# SCH_micro65_2023-10-09.net
KiCad netlist of a schematic drawn in EasyEDA
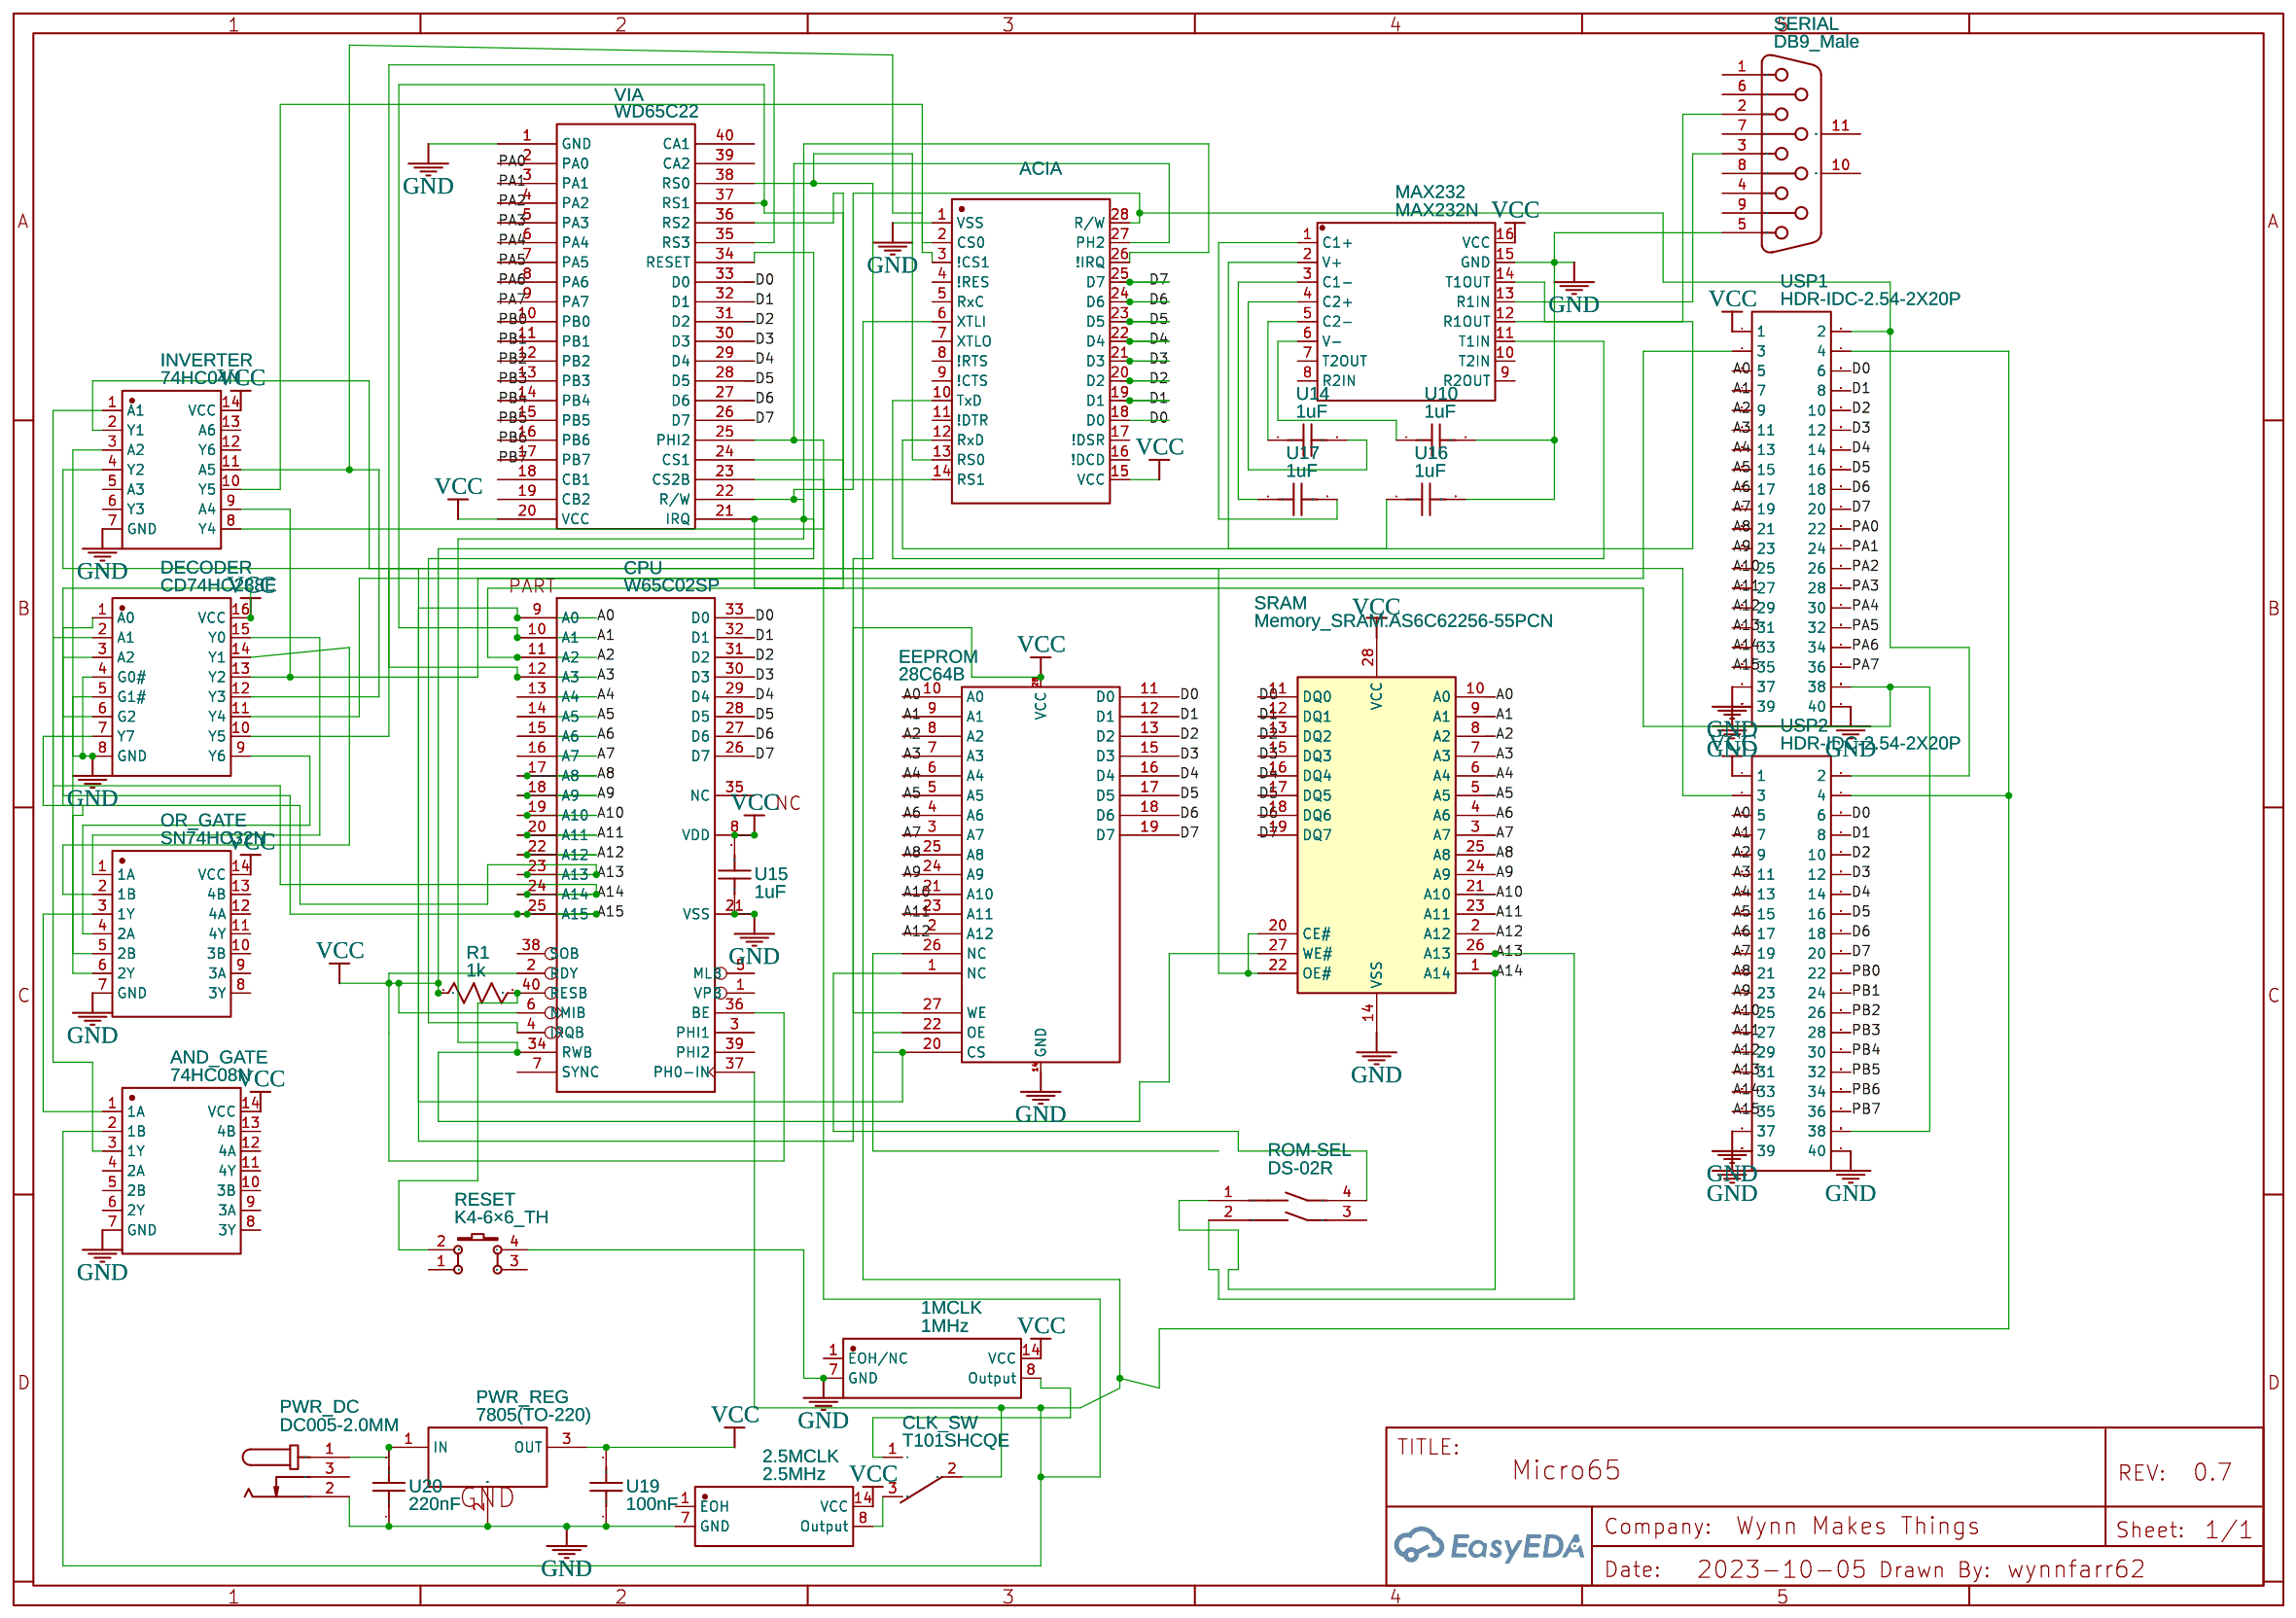
[diagram p0: schematic sheet]

(export (version "E")
  (design (tool "Eeschema 10.0.6"))
  (components
    (comp (ref "1MCLK")
      (value "1MHz")
      (fields
        (field (name "Manufacturer Part") "MXO45T-2C-1M000000")
        (field (name "Manufacturer") "CTS(西迪斯)")
      )
      (libsource (lib "") (part "MXO45T-2C-1M000000"))
    )
    (comp (ref "2.5MCLK")
      (value "2.5MHz")
      (fields
        (field (name "Manufacturer Part") "MXO45HST-2I-2M500000")
        (field (name "Manufacturer") "CTS(西迪斯)")
      )
      (libsource (lib "") (part "MXO45HST-2I-2M500000"))
    )
    (comp (ref "ACIA") (value "NO") (libsource (lib "") (part "R6551")))
    (comp (ref "AND_GATE")
      (value "74HC08N")
      (fields (field (name "Manufacturer") "HGSEMI(华冠)"))
      (libsource (lib "") (part "74HC08N"))
    )
    (comp (ref "CLK_SW")
      (value "T101SHCQE")
      (fields (field (name "Manufacturer") "C&K"))
      (libsource (lib "") (part "T101SHCQE"))
    )
    (comp (ref "CPU") (value "W65C02SP") (libsource (lib "") (part "Unknown_325_-395")))
    (comp (ref "DECODER")
      (value "CD74HC238E")
      (fields (field (name "Manufacturer") "TI(德州仪器)"))
      (libsource (lib "") (part "CD74HC238E"))
    )
    (comp (ref "EEPROM") (value "28C64B") (libsource (lib "") (part "Unknown_520_-370")))
    (comp (ref "INVERTER")
      (value "74HC04N")
      (fields (field (name "Manufacturer") "HGSEMI(华冠)"))
      (libsource (lib "") (part "74HC04N"))
    )
    (comp (ref "MAX232")
      (value "MAX232N")
      (fields (field (name "Manufacturer") "Texas Instruments"))
      (libsource (lib "") (part "MAX232N"))
    )
    (comp (ref "OR_GATE")
      (value "SN74HC32N")
      (fields (field (name "Manufacturer") "TI(德州仪器)"))
      (libsource (lib "") (part "SN74HC32N"))
    )
    (comp (ref "PWR_DC")
      (value "DC005-2.0MM")
      (fields (field (name "Manufacturer") "SOFNG"))
      (libsource (lib "") (part "DC005-2.0MM"))
    )
    (comp (ref "PWR_REG")
      (value "7805(TO-220)")
      (fields
        (field (name "Manufacturer Part") "L7805CV-DG")
        (field (name "Manufacturer") "STMicroelectronics")
      )
      (libsource (lib "") (part "7805(TO-220)"))
    )
    (comp (ref "R1") (value "1k") (libsource (lib "") (part "R_AXIAL-0.3_US")))
    (comp (ref "RESET")
      (value "K4-6×6_TH")
      (fields (field (name "Manufacturer Part") "K2-1102DP-E4SW-04") (field (name "Manufacturer") "韩国韩荣"))
      (libsource (lib "") (part "K4-6×6_TH"))
    )
    (comp (ref "ROM-SEL")
      (value "DS-02R")
      (fields (field (name "Manufacturer") "SM Switch"))
      (libsource (lib "") (part "DS-02R"))
    )
    (comp (ref "SERIAL")
      (value "DB9_Male")
      (fields (field (name "Manufacturer") "Amphenol"))
      (libsource (lib "") (part "DB9_Male"))
    )
    (comp (ref "SRAM") (value "Memory_SRAM:AS6C62256-55PCN") (libsource (lib "") (part "Unknown_690_-390")))
    (comp (ref "U10")
      (value "1uF")
      (fields (field (name "Manufacturer Part") "FK28X5R1E105KR000") (field (name "Manufacturer") "TDK"))
      (libsource (lib "") (part "FK28X5R1E105KR000_1"))
    )
    (comp (ref "U14")
      (value "1uF")
      (fields (field (name "Manufacturer Part") "FK28X5R1E105KR000") (field (name "Manufacturer") "TDK"))
      (libsource (lib "") (part "FK28X5R1E105KR000_1"))
    )
    (comp (ref "U15")
      (value "1uF")
      (fields (field (name "Manufacturer Part") "FK28X5R1E105KR000") (field (name "Manufacturer") "TDK"))
      (libsource (lib "") (part "FK28X5R1E105KR000"))
    )
    (comp (ref "U16")
      (value "1uF")
      (fields (field (name "Manufacturer Part") "FK28X5R1E105KR000") (field (name "Manufacturer") "TDK"))
      (libsource (lib "") (part "FK28X5R1E105KR000_1"))
    )
    (comp (ref "U17")
      (value "1uF")
      (fields (field (name "Manufacturer Part") "FK28X5R1E105KR000") (field (name "Manufacturer") "TDK"))
      (libsource (lib "") (part "FK28X5R1E105KR000_1"))
    )
    (comp (ref "U19")
      (value "100nF")
      (fields
        (field (name "Manufacturer Part") "MEB104J63V82CB0236")
        (field (name "Manufacturer") "KNSCHA(科尼盛)")
      )
      (libsource (lib "") (part "MEB104J63V82CB0236"))
    )
    (comp (ref "U20")
      (value "220nF")
      (fields
        (field (name "Manufacturer Part") "C242A224J20C000")
        (field (name "Manufacturer") "faratronic(厦门法拉)")
      )
      (libsource (lib "") (part "C242A224J20C000"))
    )
    (comp (ref "USP1")
      (value "HDR-IDC-2.54-2X20P")
      (fields
        (field (name "Manufacturer Part") "IDC Box 2X20 2.54MM")
        (field (name "Manufacturer") "BOOMELE")
      )
      (libsource (lib "") (part "HDR-IDC-2.54-2X20P"))
    )
    (comp (ref "USP2")
      (value "HDR-IDC-2.54-2X20P")
      (fields
        (field (name "Manufacturer Part") "IDC Box 2X20 2.54MM")
        (field (name "Manufacturer") "BOOMELE")
      )
      (libsource (lib "") (part "HDR-IDC-2.54-2X20P"))
    )
    (comp (ref "VIA") (value "WD65C22") (libsource (lib "") (part "Unknown_310_-650")))
  )
  (nets
    (net (code "1") (name "/A0") (class "Default")
      (node (ref "ACIA") (pin "13") (pinfunction "RS0_13") (pintype "unspecified"))
      (node (ref "CPU") (pin "9") (pinfunction "A0_9") (pintype "unspecified"))
      (node (ref "EEPROM") (pin "10") (pinfunction "A0_10") (pintype "input"))
      (node (ref "SRAM") (pin "10") (pinfunction "A0_10") (pintype "input"))
      (node (ref "USP1") (pin "5") (pinfunction "5_5") (pintype "unspecified"))
      (node (ref "USP2") (pin "5") (pinfunction "5_5") (pintype "unspecified"))
      (node (ref "VIA") (pin "38") (pinfunction "RS0_38") (pintype "input"))
    )
    (net (code "2") (name "/A1") (class "Default")
      (node (ref "ACIA") (pin "14") (pinfunction "RS1_14") (pintype "unspecified"))
      (node (ref "CPU") (pin "10") (pinfunction "A1_10") (pintype "unspecified"))
      (node (ref "EEPROM") (pin "9") (pinfunction "A1_9") (pintype "input"))
      (node (ref "SRAM") (pin "9") (pinfunction "A1_9") (pintype "input"))
      (node (ref "USP1") (pin "7") (pinfunction "7_7") (pintype "unspecified"))
      (node (ref "USP2") (pin "7") (pinfunction "7_7") (pintype "unspecified"))
      (node (ref "VIA") (pin "37") (pinfunction "RS1_37") (pintype "input"))
    )
    (net (code "3") (name "/A2") (class "Default")
      (node (ref "CPU") (pin "11") (pinfunction "A2_11") (pintype "unspecified"))
      (node (ref "EEPROM") (pin "8") (pinfunction "A2_8") (pintype "input"))
      (node (ref "SRAM") (pin "8") (pinfunction "A2_8") (pintype "input"))
      (node (ref "USP1") (pin "9") (pinfunction "9_9") (pintype "unspecified"))
      (node (ref "USP2") (pin "9") (pinfunction "9_9") (pintype "unspecified"))
      (node (ref "VIA") (pin "36") (pinfunction "RS2_36") (pintype "input"))
    )
    (net (code "4") (name "/A3") (class "Default")
      (node (ref "CPU") (pin "12") (pinfunction "A3_12") (pintype "unspecified"))
      (node (ref "EEPROM") (pin "7") (pinfunction "A3_7") (pintype "input"))
      (node (ref "SRAM") (pin "7") (pinfunction "A3_7") (pintype "input"))
      (node (ref "USP1") (pin "11") (pinfunction "11_11") (pintype "unspecified"))
      (node (ref "USP2") (pin "11") (pinfunction "11_11") (pintype "unspecified"))
      (node (ref "VIA") (pin "35") (pinfunction "RS3_35") (pintype "input"))
    )
    (net (code "5") (name "/A4") (class "Default")
      (node (ref "CPU") (pin "13") (pinfunction "A4_13") (pintype "unspecified"))
      (node (ref "EEPROM") (pin "6") (pinfunction "A4_6") (pintype "input"))
      (node (ref "SRAM") (pin "6") (pinfunction "A4_6") (pintype "input"))
      (node (ref "USP1") (pin "13") (pinfunction "13_13") (pintype "unspecified"))
      (node (ref "USP2") (pin "13") (pinfunction "13_13") (pintype "unspecified"))
    )
    (net (code "6") (name "/A5") (class "Default")
      (node (ref "CPU") (pin "14") (pinfunction "A5_14") (pintype "unspecified"))
      (node (ref "EEPROM") (pin "5") (pinfunction "A5_5") (pintype "input"))
      (node (ref "SRAM") (pin "5") (pinfunction "A5_5") (pintype "input"))
      (node (ref "USP1") (pin "15") (pinfunction "15_15") (pintype "unspecified"))
      (node (ref "USP2") (pin "15") (pinfunction "15_15") (pintype "unspecified"))
    )
    (net (code "7") (name "/A6") (class "Default")
      (node (ref "CPU") (pin "15") (pinfunction "A6_15") (pintype "unspecified"))
      (node (ref "EEPROM") (pin "4") (pinfunction "A6_4") (pintype "input"))
      (node (ref "SRAM") (pin "4") (pinfunction "A6_4") (pintype "input"))
      (node (ref "USP1") (pin "17") (pinfunction "17_17") (pintype "unspecified"))
      (node (ref "USP2") (pin "17") (pinfunction "17_17") (pintype "unspecified"))
    )
    (net (code "8") (name "/A7") (class "Default")
      (node (ref "CPU") (pin "16") (pinfunction "A7_16") (pintype "unspecified"))
      (node (ref "EEPROM") (pin "3") (pinfunction "A7_3") (pintype "input"))
      (node (ref "SRAM") (pin "3") (pinfunction "A7_3") (pintype "input"))
      (node (ref "USP1") (pin "19") (pinfunction "19_19") (pintype "unspecified"))
      (node (ref "USP2") (pin "19") (pinfunction "19_19") (pintype "unspecified"))
    )
    (net (code "9") (name "/A8") (class "Default")
      (node (ref "CPU") (pin "17") (pinfunction "A8_17") (pintype "unspecified"))
      (node (ref "EEPROM") (pin "25") (pinfunction "A8_25") (pintype "input"))
      (node (ref "SRAM") (pin "25") (pinfunction "A8_25") (pintype "input"))
      (node (ref "USP1") (pin "21") (pinfunction "21_21") (pintype "unspecified"))
      (node (ref "USP2") (pin "21") (pinfunction "21_21") (pintype "unspecified"))
    )
    (net (code "10") (name "/A9") (class "Default")
      (node (ref "CPU") (pin "18") (pinfunction "A9_18") (pintype "unspecified"))
      (node (ref "EEPROM") (pin "24") (pinfunction "A9_24") (pintype "input"))
      (node (ref "SRAM") (pin "24") (pinfunction "A9_24") (pintype "input"))
      (node (ref "USP1") (pin "23") (pinfunction "23_23") (pintype "unspecified"))
      (node (ref "USP2") (pin "23") (pinfunction "23_23") (pintype "unspecified"))
    )
    (net (code "11") (name "/A10") (class "Default")
      (node (ref "CPU") (pin "19") (pinfunction "A10_19") (pintype "unspecified"))
      (node (ref "EEPROM") (pin "21") (pinfunction "A10_21") (pintype "input"))
      (node (ref "SRAM") (pin "21") (pinfunction "A10_21") (pintype "input"))
      (node (ref "USP1") (pin "25") (pinfunction "25_25") (pintype "unspecified"))
      (node (ref "USP2") (pin "25") (pinfunction "25_25") (pintype "unspecified"))
    )
    (net (code "12") (name "/A11") (class "Default")
      (node (ref "CPU") (pin "20") (pinfunction "A11_20") (pintype "unspecified"))
      (node (ref "EEPROM") (pin "23") (pinfunction "A11_23") (pintype "input"))
      (node (ref "SRAM") (pin "23") (pinfunction "A11_23") (pintype "input"))
      (node (ref "USP1") (pin "27") (pinfunction "27_27") (pintype "unspecified"))
      (node (ref "USP2") (pin "27") (pinfunction "27_27") (pintype "unspecified"))
    )
    (net (code "13") (name "/A12") (class "Default")
      (node (ref "CPU") (pin "22") (pinfunction "A12_22") (pintype "unspecified"))
      (node (ref "EEPROM") (pin "2") (pinfunction "A12_2") (pintype "input"))
      (node (ref "SRAM") (pin "2") (pinfunction "A12_2") (pintype "input"))
      (node (ref "USP1") (pin "29") (pinfunction "29_29") (pintype "unspecified"))
      (node (ref "USP2") (pin "29") (pinfunction "29_29") (pintype "unspecified"))
    )
    (net (code "14") (name "/A13") (class "Default")
      (node (ref "CPU") (pin "23") (pinfunction "A13_23") (pintype "unspecified"))
      (node (ref "DECODER") (pin "1") (pinfunction "A0_1") (pintype "unspecified"))
      (node (ref "ROM-SEL") (pin "2") (pinfunction "2_2") (pintype "unspecified"))
      (node (ref "SRAM") (pin "26") (pinfunction "A13_26") (pintype "input"))
      (node (ref "USP1") (pin "31") (pinfunction "31_31") (pintype "unspecified"))
      (node (ref "USP2") (pin "31") (pinfunction "31_31") (pintype "unspecified"))
    )
    (net (code "15") (name "/A14") (class "Default")
      (node (ref "CPU") (pin "24") (pinfunction "A14_24") (pintype "unspecified"))
      (node (ref "DECODER") (pin "2") (pinfunction "A1_2") (pintype "unspecified"))
      (node (ref "ROM-SEL") (pin "1") (pinfunction "1_1") (pintype "unspecified"))
      (node (ref "SRAM") (pin "1") (pinfunction "A14_1") (pintype "input"))
      (node (ref "USP1") (pin "33") (pinfunction "33_33") (pintype "unspecified"))
      (node (ref "USP2") (pin "33") (pinfunction "33_33") (pintype "unspecified"))
    )
    (net (code "16") (name "/A15") (class "Default")
      (node (ref "CPU") (pin "25") (pinfunction "A15_25") (pintype "unspecified"))
      (node (ref "DECODER") (pin "3") (pinfunction "A2_3") (pintype "unspecified"))
      (node (ref "USP1") (pin "35") (pinfunction "35_35") (pintype "unspecified"))
      (node (ref "USP2") (pin "35") (pinfunction "35_35") (pintype "unspecified"))
    )
    (net (code "17") (name "/D0") (class "Default")
      (node (ref "ACIA") (pin "18") (pinfunction "D0_18") (pintype "unspecified"))
      (node (ref "CPU") (pin "33") (pinfunction "D0_33") (pintype "unspecified"))
      (node (ref "EEPROM") (pin "11") (pinfunction "D0_11") (pintype "bidirectional"))
      (node (ref "SRAM") (pin "11") (pinfunction "DQ0_11") (pintype "bidirectional"))
      (node (ref "USP1") (pin "6") (pinfunction "6_6") (pintype "unspecified"))
      (node (ref "USP2") (pin "6") (pinfunction "6_6") (pintype "unspecified"))
      (node (ref "VIA") (pin "33") (pinfunction "D0_33") (pintype "bidirectional"))
    )
    (net (code "18") (name "/D1") (class "Default")
      (node (ref "ACIA") (pin "19") (pinfunction "D1_19") (pintype "unspecified"))
      (node (ref "CPU") (pin "32") (pinfunction "D1_32") (pintype "unspecified"))
      (node (ref "EEPROM") (pin "12") (pinfunction "D1_12") (pintype "bidirectional"))
      (node (ref "SRAM") (pin "12") (pinfunction "DQ1_12") (pintype "bidirectional"))
      (node (ref "USP1") (pin "8") (pinfunction "8_8") (pintype "unspecified"))
      (node (ref "USP2") (pin "8") (pinfunction "8_8") (pintype "unspecified"))
      (node (ref "VIA") (pin "32") (pinfunction "D1_32") (pintype "bidirectional"))
    )
    (net (code "19") (name "/D2") (class "Default")
      (node (ref "ACIA") (pin "20") (pinfunction "D2_20") (pintype "unspecified"))
      (node (ref "CPU") (pin "31") (pinfunction "D2_31") (pintype "unspecified"))
      (node (ref "EEPROM") (pin "13") (pinfunction "D2_13") (pintype "bidirectional"))
      (node (ref "SRAM") (pin "13") (pinfunction "DQ2_13") (pintype "bidirectional"))
      (node (ref "USP1") (pin "10") (pinfunction "10_10") (pintype "unspecified"))
      (node (ref "USP2") (pin "10") (pinfunction "10_10") (pintype "unspecified"))
      (node (ref "VIA") (pin "31") (pinfunction "D2_31") (pintype "bidirectional"))
    )
    (net (code "20") (name "/D3") (class "Default")
      (node (ref "ACIA") (pin "21") (pinfunction "D3_21") (pintype "unspecified"))
      (node (ref "CPU") (pin "30") (pinfunction "D3_30") (pintype "unspecified"))
      (node (ref "EEPROM") (pin "15") (pinfunction "D3_15") (pintype "bidirectional"))
      (node (ref "SRAM") (pin "15") (pinfunction "DQ3_15") (pintype "bidirectional"))
      (node (ref "USP1") (pin "12") (pinfunction "12_12") (pintype "unspecified"))
      (node (ref "USP2") (pin "12") (pinfunction "12_12") (pintype "unspecified"))
      (node (ref "VIA") (pin "30") (pinfunction "D3_30") (pintype "bidirectional"))
    )
    (net (code "21") (name "/D4") (class "Default")
      (node (ref "ACIA") (pin "22") (pinfunction "D4_22") (pintype "unspecified"))
      (node (ref "CPU") (pin "29") (pinfunction "D4_29") (pintype "unspecified"))
      (node (ref "EEPROM") (pin "16") (pinfunction "D4_16") (pintype "bidirectional"))
      (node (ref "SRAM") (pin "16") (pinfunction "DQ4_16") (pintype "bidirectional"))
      (node (ref "USP1") (pin "14") (pinfunction "14_14") (pintype "unspecified"))
      (node (ref "USP2") (pin "14") (pinfunction "14_14") (pintype "unspecified"))
      (node (ref "VIA") (pin "29") (pinfunction "D4_29") (pintype "bidirectional"))
    )
    (net (code "22") (name "/D5") (class "Default")
      (node (ref "ACIA") (pin "23") (pinfunction "D5_23") (pintype "unspecified"))
      (node (ref "CPU") (pin "28") (pinfunction "D5_28") (pintype "unspecified"))
      (node (ref "EEPROM") (pin "17") (pinfunction "D5_17") (pintype "bidirectional"))
      (node (ref "SRAM") (pin "17") (pinfunction "DQ5_17") (pintype "bidirectional"))
      (node (ref "USP1") (pin "16") (pinfunction "16_16") (pintype "unspecified"))
      (node (ref "USP2") (pin "16") (pinfunction "16_16") (pintype "unspecified"))
      (node (ref "VIA") (pin "28") (pinfunction "D5_28") (pintype "bidirectional"))
    )
    (net (code "23") (name "/D6") (class "Default")
      (node (ref "ACIA") (pin "24") (pinfunction "D6_24") (pintype "unspecified"))
      (node (ref "CPU") (pin "27") (pinfunction "D6_27") (pintype "unspecified"))
      (node (ref "EEPROM") (pin "18") (pinfunction "D6_18") (pintype "bidirectional"))
      (node (ref "SRAM") (pin "18") (pinfunction "DQ6_18") (pintype "bidirectional"))
      (node (ref "USP1") (pin "18") (pinfunction "18_18") (pintype "unspecified"))
      (node (ref "USP2") (pin "18") (pinfunction "18_18") (pintype "unspecified"))
      (node (ref "VIA") (pin "27") (pinfunction "D6_27") (pintype "bidirectional"))
    )
    (net (code "24") (name "/D7") (class "Default")
      (node (ref "ACIA") (pin "25") (pinfunction "D7_25") (pintype "unspecified"))
      (node (ref "CPU") (pin "26") (pinfunction "D7_26") (pintype "unspecified"))
      (node (ref "EEPROM") (pin "19") (pinfunction "D7_19") (pintype "bidirectional"))
      (node (ref "SRAM") (pin "19") (pinfunction "DQ7_19") (pintype "bidirectional"))
      (node (ref "USP1") (pin "20") (pinfunction "20_20") (pintype "unspecified"))
      (node (ref "USP2") (pin "20") (pinfunction "20_20") (pintype "unspecified"))
      (node (ref "VIA") (pin "26") (pinfunction "D7_26") (pintype "bidirectional"))
    )
    (net (code "25") (name "/PA0") (class "Default")
      (node (ref "USP1") (pin "22") (pinfunction "22_22") (pintype "unspecified"))
      (node (ref "VIA") (pin "2") (pinfunction "PA0_2") (pintype "bidirectional"))
    )
    (net (code "26") (name "/PA1") (class "Default")
      (node (ref "USP1") (pin "24") (pinfunction "24_24") (pintype "unspecified"))
      (node (ref "VIA") (pin "3") (pinfunction "PA1_3") (pintype "bidirectional"))
    )
    (net (code "27") (name "/PA2") (class "Default")
      (node (ref "USP1") (pin "26") (pinfunction "26_26") (pintype "unspecified"))
      (node (ref "VIA") (pin "4") (pinfunction "PA2_4") (pintype "bidirectional"))
    )
    (net (code "28") (name "/PA3") (class "Default")
      (node (ref "USP1") (pin "28") (pinfunction "28_28") (pintype "unspecified"))
      (node (ref "VIA") (pin "5") (pinfunction "PA3_5") (pintype "bidirectional"))
    )
    (net (code "29") (name "/PA4") (class "Default")
      (node (ref "USP1") (pin "30") (pinfunction "30_30") (pintype "unspecified"))
      (node (ref "VIA") (pin "6") (pinfunction "PA4_6") (pintype "bidirectional"))
    )
    (net (code "30") (name "/PA5") (class "Default")
      (node (ref "USP1") (pin "32") (pinfunction "32_32") (pintype "unspecified"))
      (node (ref "VIA") (pin "7") (pinfunction "PA5_7") (pintype "bidirectional"))
    )
    (net (code "31") (name "/PA6") (class "Default")
      (node (ref "USP1") (pin "34") (pinfunction "34_34") (pintype "unspecified"))
      (node (ref "VIA") (pin "8") (pinfunction "PA6_8") (pintype "bidirectional"))
    )
    (net (code "32") (name "/PA7") (class "Default")
      (node (ref "USP1") (pin "36") (pinfunction "36_36") (pintype "unspecified"))
      (node (ref "VIA") (pin "9") (pinfunction "PA7_9") (pintype "bidirectional"))
    )
    (net (code "33") (name "/PB0") (class "Default")
      (node (ref "USP2") (pin "22") (pinfunction "22_22") (pintype "unspecified"))
      (node (ref "VIA") (pin "10") (pinfunction "PB0_10") (pintype "bidirectional"))
    )
    (net (code "34") (name "/PB1") (class "Default")
      (node (ref "USP2") (pin "24") (pinfunction "24_24") (pintype "unspecified"))
      (node (ref "VIA") (pin "11") (pinfunction "PB1_11") (pintype "bidirectional"))
    )
    (net (code "35") (name "/PB2") (class "Default")
      (node (ref "USP2") (pin "26") (pinfunction "26_26") (pintype "unspecified"))
      (node (ref "VIA") (pin "12") (pinfunction "PB2_12") (pintype "bidirectional"))
    )
    (net (code "36") (name "/PB3") (class "Default")
      (node (ref "USP2") (pin "28") (pinfunction "28_28") (pintype "unspecified"))
      (node (ref "VIA") (pin "13") (pinfunction "PB3_13") (pintype "bidirectional"))
    )
    (net (code "37") (name "/PB4") (class "Default")
      (node (ref "USP2") (pin "30") (pinfunction "30_30") (pintype "unspecified"))
      (node (ref "VIA") (pin "14") (pinfunction "PB4_14") (pintype "bidirectional"))
    )
    (net (code "38") (name "/PB5") (class "Default")
      (node (ref "USP2") (pin "32") (pinfunction "32_32") (pintype "unspecified"))
      (node (ref "VIA") (pin "15") (pinfunction "PB5_15") (pintype "bidirectional"))
    )
    (net (code "39") (name "/PB6") (class "Default")
      (node (ref "USP2") (pin "34") (pinfunction "34_34") (pintype "unspecified"))
      (node (ref "VIA") (pin "16") (pinfunction "PB6_16") (pintype "bidirectional"))
    )
    (net (code "40") (name "/PB7") (class "Default")
      (node (ref "USP2") (pin "36") (pinfunction "36_36") (pintype "unspecified"))
      (node (ref "VIA") (pin "17") (pinfunction "PB7_17") (pintype "bidirectional"))
    )
    (net (code "41") (name "GND") (class "Default")
      (node (ref "1MCLK") (pin "7") (pinfunction "GND_7") (pintype "unspecified"))
      (node (ref "2.5MCLK") (pin "7") (pinfunction "GND_7") (pintype "unspecified"))
      (node (ref "ACIA") (pin "1") (pinfunction "VSS_1") (pintype "unspecified"))
      (node (ref "AND_GATE") (pin "7") (pinfunction "GND_7") (pintype "unspecified"))
      (node (ref "CPU") (pin "21") (pinfunction "VSS_21") (pintype "unspecified"))
      (node (ref "DECODER") (pin "4") (pinfunction "G0#_4") (pintype "unspecified"))
      (node (ref "DECODER") (pin "5") (pinfunction "G1#_5") (pintype "unspecified"))
      (node (ref "DECODER") (pin "8") (pinfunction "GND_8") (pintype "unspecified"))
      (node (ref "EEPROM") (pin "14") (pinfunction "GND_14") (pintype "passive"))
      (node (ref "INVERTER") (pin "7") (pinfunction "GND_7") (pintype "unspecified"))
      (node (ref "MAX232") (pin "15") (pinfunction "GND_15") (pintype "unspecified"))
      (node (ref "OR_GATE") (pin "7") (pinfunction "GND_7") (pintype "unspecified"))
      (node (ref "PWR_DC") (pin "2") (pinfunction "2_2") (pintype "unspecified"))
      (node (ref "PWR_REG") (pin "2") (pinfunction "GND_2") (pintype "passive"))
      (node (ref "RESET") (pin "4") (pinfunction "4_4") (pintype "unspecified"))
      (node (ref "SERIAL") (pin "5") (pinfunction "5_5") (pintype "input"))
      (node (ref "SRAM") (pin "14") (pinfunction "VSS_14") (pintype "bidirectional"))
      (node (ref "U10") (pin "2") (pinfunction "2_2") (pintype "unspecified"))
      (node (ref "U15") (pin "1") (pinfunction "1_1") (pintype "unspecified"))
      (node (ref "U16") (pin "2") (pinfunction "2_2") (pintype "unspecified"))
      (node (ref "U19") (pin "1") (pinfunction "1_1") (pintype "unspecified"))
      (node (ref "U20") (pin "1") (pinfunction "1_1") (pintype "unspecified"))
      (node (ref "USP1") (pin "37") (pinfunction "37_37") (pintype "unspecified"))
      (node (ref "USP1") (pin "39") (pinfunction "39_39") (pintype "unspecified"))
      (node (ref "USP1") (pin "40") (pinfunction "40_40") (pintype "unspecified"))
      (node (ref "USP2") (pin "37") (pinfunction "37_37") (pintype "unspecified"))
      (node (ref "USP2") (pin "39") (pinfunction "39_39") (pintype "unspecified"))
      (node (ref "USP2") (pin "40") (pinfunction "40_40") (pintype "unspecified"))
      (node (ref "VIA") (pin "1") (pinfunction "GND_1") (pintype "output"))
    )
    (net (code "42") (name "Net-(1MCLK-Output)") (class "Default")
      (node (ref "1MCLK") (pin "8") (pinfunction "Output_8") (pintype "unspecified"))
      (node (ref "CLK_SW") (pin "1") (pinfunction "1_1") (pintype "unspecified"))
    )
    (net (code "43") (name "Net-(2.5MCLK-Output)") (class "Default")
      (node (ref "2.5MCLK") (pin "8") (pinfunction "Output_8") (pintype "unspecified"))
      (node (ref "CLK_SW") (pin "3") (pinfunction "3_3") (pintype "unspecified"))
    )
    (net (code "44") (name "Net-(ACIA-!CS1)") (class "Default")
      (node (ref "ACIA") (pin "3") (pinfunction "!CS1_3") (pintype "unspecified"))
      (node (ref "INVERTER") (pin "10") (pinfunction "Y5_10") (pintype "unspecified"))
    )
    (net (code "45") (name "Net-(ACIA-!IRQ)") (class "Default")
      (node (ref "ACIA") (pin "26") (pinfunction "!IRQ_26") (pintype "unspecified"))
      (node (ref "ACIA") (pin "28") (pinfunction "R/W_28") (pintype "unspecified"))
      (node (ref "CPU") (pin "34") (pinfunction "RWB_34") (pintype "output"))
      (node (ref "CPU") (pin "4") (pinfunction "IRQB_4") (pintype "input"))
      (node (ref "SRAM") (pin "27") (pinfunction "WE#_27") (pintype "input"))
      (node (ref "USP1") (pin "2") (pinfunction "2_2") (pintype "unspecified"))
      (node (ref "USP1") (pin "38") (pinfunction "38_38") (pintype "unspecified"))
      (node (ref "USP2") (pin "2") (pinfunction "2_2") (pintype "unspecified"))
      (node (ref "USP2") (pin "38") (pinfunction "38_38") (pintype "unspecified"))
      (node (ref "VIA") (pin "21") (pinfunction "IRQ_21") (pintype "output"))
      (node (ref "VIA") (pin "22") (pinfunction "R/W_22") (pintype "input"))
    )
    (net (code "46") (name "Net-(ACIA-CS0)") (class "Default")
      (node (ref "ACIA") (pin "2") (pinfunction "CS0_2") (pintype "unspecified"))
      (node (ref "DECODER") (pin "12") (pinfunction "Y3_12") (pintype "unspecified"))
      (node (ref "INVERTER") (pin "11") (pinfunction "A5_11") (pintype "unspecified"))
    )
    (net (code "47") (name "Net-(ACIA-PH2)") (class "Default")
      (node (ref "ACIA") (pin "27") (pinfunction "PH2_27") (pintype "unspecified"))
      (node (ref "ACIA") (pin "6") (pinfunction "XTLI_6") (pintype "unspecified"))
      (node (ref "AND_GATE") (pin "2") (pinfunction "1B_2") (pintype "unspecified"))
      (node (ref "CLK_SW") (pin "2") (pinfunction "2_2") (pintype "unspecified"))
      (node (ref "CPU") (pin "37") (pinfunction "PH0-IN_37") (pintype "input"))
      (node (ref "USP1") (pin "4") (pinfunction "4_4") (pintype "unspecified"))
      (node (ref "USP2") (pin "4") (pinfunction "4_4") (pintype "unspecified"))
      (node (ref "VIA") (pin "25") (pinfunction "PHI2_25") (pintype "input"))
    )
    (net (code "48") (name "Net-(ACIA-RxD)") (class "Default")
      (node (ref "ACIA") (pin "12") (pinfunction "RxD_12") (pintype "unspecified"))
      (node (ref "MAX232") (pin "12") (pinfunction "R1OUT_12") (pintype "unspecified"))
    )
    (net (code "49") (name "Net-(ACIA-TxD)") (class "Default")
      (node (ref "ACIA") (pin "10") (pinfunction "TxD_10") (pintype "unspecified"))
      (node (ref "MAX232") (pin "11") (pinfunction "T1IN_11") (pintype "unspecified"))
    )
    (net (code "50") (name "Net-(AND_GATE-1A)") (class "Default")
      (node (ref "AND_GATE") (pin "1") (pinfunction "1A_1") (pintype "unspecified"))
      (node (ref "OR_GATE") (pin "3") (pinfunction "1Y_3") (pintype "unspecified"))
    )
    (net (code "51") (name "Net-(AND_GATE-1Y)") (class "Default")
      (node (ref "AND_GATE") (pin "3") (pinfunction "1Y_3") (pintype "unspecified"))
      (node (ref "INVERTER") (pin "1") (pinfunction "A1_1") (pintype "unspecified"))
    )
    (net (code "52") (name "Net-(CPU-RESB)") (class "Default")
      (node (ref "CPU") (pin "40") (pinfunction "RESB_40") (pintype "input"))
      (node (ref "R1") (pin "2") (pinfunction "2_2") (pintype "unspecified"))
      (node (ref "RESET") (pin "2") (pinfunction "2_2") (pintype "unspecified"))
    )
    (net (code "53") (name "Net-(DECODER-Y0)") (class "Default")
      (node (ref "DECODER") (pin "15") (pinfunction "Y0_15") (pintype "unspecified"))
      (node (ref "OR_GATE") (pin "1") (pinfunction "1A_1") (pintype "unspecified"))
    )
    (net (code "54") (name "Net-(DECODER-Y1)") (class "Default")
      (node (ref "DECODER") (pin "14") (pinfunction "Y1_14") (pintype "unspecified"))
      (node (ref "OR_GATE") (pin "2") (pinfunction "1B_2") (pintype "unspecified"))
    )
    (net (code "55") (name "Net-(DECODER-Y2)") (class "Default")
      (node (ref "DECODER") (pin "13") (pinfunction "Y2_13") (pintype "unspecified"))
      (node (ref "INVERTER") (pin "9") (pinfunction "A4_9") (pintype "unspecified"))
      (node (ref "VIA") (pin "24") (pinfunction "CS1_24") (pintype "input"))
    )
    (net (code "56") (name "Net-(DECODER-Y4)") (class "Default")
      (node (ref "DECODER") (pin "11") (pinfunction "Y4_11") (pintype "unspecified"))
      (node (ref "USP1") (pin "3") (pinfunction "3_3") (pintype "unspecified"))
    )
    (net (code "57") (name "Net-(DECODER-Y5)") (class "Default")
      (node (ref "DECODER") (pin "10") (pinfunction "Y5_10") (pintype "unspecified"))
      (node (ref "USP2") (pin "3") (pinfunction "3_3") (pintype "unspecified"))
    )
    (net (code "58") (name "Net-(DECODER-Y6)") (class "Default")
      (node (ref "DECODER") (pin "9") (pinfunction "Y6_9") (pintype "unspecified"))
      (node (ref "OR_GATE") (pin "4") (pinfunction "2A_4") (pintype "unspecified"))
    )
    (net (code "59") (name "Net-(DECODER-Y7)") (class "Default")
      (node (ref "DECODER") (pin "7") (pinfunction "Y7_7") (pintype "unspecified"))
      (node (ref "OR_GATE") (pin "5") (pinfunction "2B_5") (pintype "unspecified"))
    )
    (net (code "60") (name "Net-(EEPROM-CS)") (class "Default")
      (node (ref "EEPROM") (pin "20") (pinfunction "CS_20") (pintype "input"))
      (node (ref "EEPROM") (pin "22") (pinfunction "OE_22") (pintype "input"))
      (node (ref "INVERTER") (pin "4") (pinfunction "Y2_4") (pintype "unspecified"))
    )
    (net (code "61") (name "Net-(EEPROM-NC-Pad1)") (class "Default")
      (node (ref "EEPROM") (pin "1") (pinfunction "NC_1") (pintype "unspecified"))
      (node (ref "ROM-SEL") (pin "4") (pinfunction "4_4") (pintype "unspecified"))
    )
    (net (code "62") (name "Net-(INVERTER-A2)") (class "Default")
      (node (ref "INVERTER") (pin "3") (pinfunction "A2_3") (pintype "unspecified"))
      (node (ref "OR_GATE") (pin "6") (pinfunction "2Y_6") (pintype "unspecified"))
    )
    (net (code "63") (name "Net-(INVERTER-Y1)") (class "Default")
      (node (ref "INVERTER") (pin "2") (pinfunction "Y1_2") (pintype "unspecified"))
      (node (ref "SRAM") (pin "20") (pinfunction "CE#_20") (pintype "input"))
      (node (ref "SRAM") (pin "22") (pinfunction "OE#_22") (pintype "input"))
    )
    (net (code "64") (name "Net-(INVERTER-Y4)") (class "Default")
      (node (ref "INVERTER") (pin "8") (pinfunction "Y4_8") (pintype "unspecified"))
      (node (ref "VIA") (pin "23") (pinfunction "CS2B_23") (pintype "input"))
    )
    (net (code "65") (name "Net-(MAX232-C1+)") (class "Default")
      (node (ref "MAX232") (pin "1") (pinfunction "C1+_1") (pintype "unspecified"))
      (node (ref "U17") (pin "2") (pinfunction "2_2") (pintype "unspecified"))
    )
    (net (code "66") (name "Net-(MAX232-C1-)") (class "Default")
      (node (ref "MAX232") (pin "3") (pinfunction "C1-_3") (pintype "unspecified"))
      (node (ref "U17") (pin "1") (pinfunction "1_1") (pintype "unspecified"))
    )
    (net (code "67") (name "Net-(MAX232-C2+)") (class "Default")
      (node (ref "MAX232") (pin "4") (pinfunction "C2+_4") (pintype "unspecified"))
      (node (ref "U14") (pin "2") (pinfunction "2_2") (pintype "unspecified"))
    )
    (net (code "68") (name "Net-(MAX232-C2-)") (class "Default")
      (node (ref "MAX232") (pin "5") (pinfunction "C2-_5") (pintype "unspecified"))
      (node (ref "U14") (pin "1") (pinfunction "1_1") (pintype "unspecified"))
    )
    (net (code "69") (name "Net-(MAX232-R1IN)") (class "Default")
      (node (ref "MAX232") (pin "13") (pinfunction "R1IN_13") (pintype "unspecified"))
      (node (ref "SERIAL") (pin "3") (pinfunction "3_3") (pintype "input"))
    )
    (net (code "70") (name "Net-(MAX232-T1OUT)") (class "Default")
      (node (ref "MAX232") (pin "14") (pinfunction "T1OUT_14") (pintype "unspecified"))
      (node (ref "SERIAL") (pin "2") (pinfunction "2_2") (pintype "input"))
    )
    (net (code "71") (name "Net-(MAX232-V+)") (class "Default")
      (node (ref "MAX232") (pin "2") (pinfunction "V+_2") (pintype "unspecified"))
      (node (ref "U16") (pin "1") (pinfunction "1_1") (pintype "unspecified"))
    )
    (net (code "72") (name "Net-(MAX232-V-)") (class "Default")
      (node (ref "MAX232") (pin "6") (pinfunction "V-_6") (pintype "unspecified"))
      (node (ref "U10") (pin "1") (pinfunction "1_1") (pintype "unspecified"))
    )
    (net (code "73") (name "Net-(PWR_REG-IN)") (class "Default")
      (node (ref "PWR_DC") (pin "1") (pinfunction "1_1") (pintype "unspecified"))
      (node (ref "PWR_REG") (pin "1") (pinfunction "IN_1") (pintype "passive"))
      (node (ref "U20") (pin "2") (pinfunction "2_2") (pintype "unspecified"))
    )
    (net (code "74") (name "VCC") (class "Default")
      (node (ref "1MCLK") (pin "14") (pinfunction "VCC_14") (pintype "unspecified"))
      (node (ref "2.5MCLK") (pin "14") (pinfunction "VCC_14") (pintype "unspecified"))
      (node (ref "ACIA") (pin "15") (pinfunction "VCC_15") (pintype "unspecified"))
      (node (ref "AND_GATE") (pin "14") (pinfunction "VCC_14") (pintype "unspecified"))
      (node (ref "CPU") (pin "2") (pinfunction "RDY_2") (pintype "unspecified"))
      (node (ref "CPU") (pin "36") (pinfunction "BE_36") (pintype "input"))
      (node (ref "CPU") (pin "6") (pinfunction "NMIB_6") (pintype "input"))
      (node (ref "CPU") (pin "8") (pinfunction "VDD_8") (pintype "passive"))
      (node (ref "DECODER") (pin "16") (pinfunction "VCC_16") (pintype "unspecified"))
      (node (ref "DECODER") (pin "6") (pinfunction "G2_6") (pintype "unspecified"))
      (node (ref "EEPROM") (pin "27") (pinfunction "WE_27") (pintype "input"))
      (node (ref "EEPROM") (pin "28") (pinfunction "VCC_28") (pintype "passive"))
      (node (ref "INVERTER") (pin "14") (pinfunction "VCC_14") (pintype "unspecified"))
      (node (ref "MAX232") (pin "16") (pinfunction "VCC_16") (pintype "unspecified"))
      (node (ref "OR_GATE") (pin "14") (pinfunction "VCC_14") (pintype "unspecified"))
      (node (ref "PWR_REG") (pin "3") (pinfunction "OUT_3") (pintype "passive"))
      (node (ref "R1") (pin "1") (pinfunction "1_1") (pintype "unspecified"))
      (node (ref "SRAM") (pin "28") (pinfunction "VCC_28") (pintype "bidirectional"))
      (node (ref "U15") (pin "2") (pinfunction "2_2") (pintype "unspecified"))
      (node (ref "U19") (pin "2") (pinfunction "2_2") (pintype "unspecified"))
      (node (ref "USP1") (pin "1") (pinfunction "1_1") (pintype "unspecified"))
      (node (ref "USP2") (pin "1") (pinfunction "1_1") (pintype "unspecified"))
      (node (ref "VIA") (pin "20") (pinfunction "VCC_20") (pintype "bidirectional"))
      (node (ref "VIA") (pin "34") (pinfunction "RESET_34") (pintype "input"))
    )
    (net (code "75") (name "unconnected-(1MCLK-EOH{slash}NC-Pad1)") (class "Default")
      (node (ref "1MCLK") (pin "1") (pinfunction "EOH/NC_1") (pintype "unspecified"))
    )
    (net (code "76") (name "unconnected-(2.5MCLK-EOH-Pad1)") (class "Default")
      (node (ref "2.5MCLK") (pin "1") (pinfunction "EOH_1") (pintype "unspecified"))
    )
    (net (code "77") (name "unconnected-(ACIA-!CTS-Pad9)") (class "Default")
      (node (ref "ACIA") (pin "9") (pinfunction "!CTS_9") (pintype "unspecified"))
    )
    (net (code "78") (name "unconnected-(ACIA-!DCD-Pad16)") (class "Default")
      (node (ref "ACIA") (pin "16") (pinfunction "!DCD_16") (pintype "unspecified"))
    )
    (net (code "79") (name "unconnected-(ACIA-!DSR-Pad17)") (class "Default")
      (node (ref "ACIA") (pin "17") (pinfunction "!DSR_17") (pintype "unspecified"))
    )
    (net (code "80") (name "unconnected-(ACIA-!DTR-Pad11)") (class "Default")
      (node (ref "ACIA") (pin "11") (pinfunction "!DTR_11") (pintype "unspecified"))
    )
    (net (code "81") (name "unconnected-(ACIA-!RES-Pad4)") (class "Default")
      (node (ref "ACIA") (pin "4") (pinfunction "!RES_4") (pintype "unspecified"))
    )
    (net (code "82") (name "unconnected-(ACIA-!RTS-Pad8)") (class "Default")
      (node (ref "ACIA") (pin "8") (pinfunction "!RTS_8") (pintype "unspecified"))
    )
    (net (code "83") (name "unconnected-(ACIA-RxC-Pad5)") (class "Default")
      (node (ref "ACIA") (pin "5") (pinfunction "RxC_5") (pintype "unspecified"))
    )
    (net (code "84") (name "unconnected-(ACIA-XTLO-Pad7)") (class "Default")
      (node (ref "ACIA") (pin "7") (pinfunction "XTLO_7") (pintype "unspecified"))
    )
    (net (code "85") (name "unconnected-(AND_GATE-2A-Pad4)") (class "Default")
      (node (ref "AND_GATE") (pin "4") (pinfunction "2A_4") (pintype "unspecified"))
    )
    (net (code "86") (name "unconnected-(AND_GATE-2B-Pad5)") (class "Default")
      (node (ref "AND_GATE") (pin "5") (pinfunction "2B_5") (pintype "unspecified"))
    )
    (net (code "87") (name "unconnected-(AND_GATE-2Y-Pad6)") (class "Default")
      (node (ref "AND_GATE") (pin "6") (pinfunction "2Y_6") (pintype "unspecified"))
    )
    (net (code "88") (name "unconnected-(AND_GATE-3A-Pad9)") (class "Default")
      (node (ref "AND_GATE") (pin "9") (pinfunction "3A_9") (pintype "unspecified"))
    )
    (net (code "89") (name "unconnected-(AND_GATE-3B-Pad10)") (class "Default")
      (node (ref "AND_GATE") (pin "10") (pinfunction "3B_10") (pintype "unspecified"))
    )
    (net (code "90") (name "unconnected-(AND_GATE-3Y-Pad8)") (class "Default")
      (node (ref "AND_GATE") (pin "8") (pinfunction "3Y_8") (pintype "unspecified"))
    )
    (net (code "91") (name "unconnected-(AND_GATE-4A-Pad12)") (class "Default")
      (node (ref "AND_GATE") (pin "12") (pinfunction "4A_12") (pintype "unspecified"))
    )
    (net (code "92") (name "unconnected-(AND_GATE-4B-Pad13)") (class "Default")
      (node (ref "AND_GATE") (pin "13") (pinfunction "4B_13") (pintype "unspecified"))
    )
    (net (code "93") (name "unconnected-(AND_GATE-4Y-Pad11)") (class "Default")
      (node (ref "AND_GATE") (pin "11") (pinfunction "4Y_11") (pintype "unspecified"))
    )
    (net (code "94") (name "unconnected-(CPU-MLB-Pad5)") (class "Default")
      (node (ref "CPU") (pin "5") (pinfunction "MLB_5") (pintype "output"))
    )
    (net (code "95") (name "unconnected-(CPU-NC-Pad35)") (class "Default")
      (node (ref "CPU") (pin "35") (pinfunction "NC_35") (pintype "unspecified"))
    )
    (net (code "96") (name "unconnected-(CPU-PHI1-Pad3)") (class "Default")
      (node (ref "CPU") (pin "3") (pinfunction "PHI1_3") (pintype "output"))
    )
    (net (code "97") (name "unconnected-(CPU-PHI2-Pad39)") (class "Default")
      (node (ref "CPU") (pin "39") (pinfunction "PHI2_39") (pintype "output"))
    )
    (net (code "98") (name "unconnected-(CPU-SOB-Pad38)") (class "Default")
      (node (ref "CPU") (pin "38") (pinfunction "SOB_38") (pintype "input"))
    )
    (net (code "99") (name "unconnected-(CPU-SYNC-Pad7)") (class "Default")
      (node (ref "CPU") (pin "7") (pinfunction "SYNC_7") (pintype "output"))
    )
    (net (code "100") (name "unconnected-(CPU-VPB-Pad1)") (class "Default")
      (node (ref "CPU") (pin "1") (pinfunction "VPB_1") (pintype "output"))
    )
    (net (code "101") (name "unconnected-(EEPROM-NC-Pad26)") (class "Default")
      (node (ref "EEPROM") (pin "26") (pinfunction "NC_26") (pintype "unspecified"))
    )
    (net (code "102") (name "unconnected-(INVERTER-A3-Pad5)") (class "Default")
      (node (ref "INVERTER") (pin "5") (pinfunction "A3_5") (pintype "unspecified"))
    )
    (net (code "103") (name "unconnected-(INVERTER-A6-Pad13)") (class "Default")
      (node (ref "INVERTER") (pin "13") (pinfunction "A6_13") (pintype "unspecified"))
    )
    (net (code "104") (name "unconnected-(INVERTER-Y3-Pad6)") (class "Default")
      (node (ref "INVERTER") (pin "6") (pinfunction "Y3_6") (pintype "unspecified"))
    )
    (net (code "105") (name "unconnected-(INVERTER-Y6-Pad12)") (class "Default")
      (node (ref "INVERTER") (pin "12") (pinfunction "Y6_12") (pintype "unspecified"))
    )
    (net (code "106") (name "unconnected-(MAX232-R2IN-Pad8)") (class "Default")
      (node (ref "MAX232") (pin "8") (pinfunction "R2IN_8") (pintype "unspecified"))
    )
    (net (code "107") (name "unconnected-(MAX232-R2OUT-Pad9)") (class "Default")
      (node (ref "MAX232") (pin "9") (pinfunction "R2OUT_9") (pintype "unspecified"))
    )
    (net (code "108") (name "unconnected-(MAX232-T2IN-Pad10)") (class "Default")
      (node (ref "MAX232") (pin "10") (pinfunction "T2IN_10") (pintype "unspecified"))
    )
    (net (code "109") (name "unconnected-(MAX232-T2OUT-Pad7)") (class "Default")
      (node (ref "MAX232") (pin "7") (pinfunction "T2OUT_7") (pintype "unspecified"))
    )
    (net (code "110") (name "unconnected-(OR_GATE-3A-Pad9)") (class "Default")
      (node (ref "OR_GATE") (pin "9") (pinfunction "3A_9") (pintype "unspecified"))
    )
    (net (code "111") (name "unconnected-(OR_GATE-3B-Pad10)") (class "Default")
      (node (ref "OR_GATE") (pin "10") (pinfunction "3B_10") (pintype "unspecified"))
    )
    (net (code "112") (name "unconnected-(OR_GATE-3Y-Pad8)") (class "Default")
      (node (ref "OR_GATE") (pin "8") (pinfunction "3Y_8") (pintype "unspecified"))
    )
    (net (code "113") (name "unconnected-(OR_GATE-4A-Pad12)") (class "Default")
      (node (ref "OR_GATE") (pin "12") (pinfunction "4A_12") (pintype "unspecified"))
    )
    (net (code "114") (name "unconnected-(OR_GATE-4B-Pad13)") (class "Default")
      (node (ref "OR_GATE") (pin "13") (pinfunction "4B_13") (pintype "unspecified"))
    )
    (net (code "115") (name "unconnected-(OR_GATE-4Y-Pad11)") (class "Default")
      (node (ref "OR_GATE") (pin "11") (pinfunction "4Y_11") (pintype "unspecified"))
    )
    (net (code "116") (name "unconnected-(PWR_DC-Pad3)") (class "Default")
      (node (ref "PWR_DC") (pin "3") (pinfunction "3_3") (pintype "unspecified"))
    )
    (net (code "117") (name "unconnected-(RESET-Pad1)") (class "Default")
      (node (ref "RESET") (pin "1") (pinfunction "1_1") (pintype "unspecified"))
    )
    (net (code "118") (name "unconnected-(RESET-Pad3)") (class "Default")
      (node (ref "RESET") (pin "3") (pinfunction "3_3") (pintype "unspecified"))
    )
    (net (code "119") (name "unconnected-(ROM-SEL-Pad3)") (class "Default")
      (node (ref "ROM-SEL") (pin "3") (pinfunction "3_3") (pintype "unspecified"))
    )
    (net (code "120") (name "unconnected-(SERIAL-MH1-Pad10)") (class "Default")
      (node (ref "SERIAL") (pin "10") (pinfunction "MH1_10") (pintype "input"))
    )
    (net (code "121") (name "unconnected-(SERIAL-MH2-Pad11)") (class "Default")
      (node (ref "SERIAL") (pin "11") (pinfunction "MH2_11") (pintype "input"))
    )
    (net (code "122") (name "unconnected-(SERIAL-Pad1)") (class "Default")
      (node (ref "SERIAL") (pin "1") (pinfunction "1_1") (pintype "input"))
    )
    (net (code "123") (name "unconnected-(SERIAL-Pad4)") (class "Default")
      (node (ref "SERIAL") (pin "4") (pinfunction "4_4") (pintype "input"))
    )
    (net (code "124") (name "unconnected-(SERIAL-Pad6)") (class "Default")
      (node (ref "SERIAL") (pin "6") (pinfunction "6_6") (pintype "input"))
    )
    (net (code "125") (name "unconnected-(SERIAL-Pad7)") (class "Default")
      (node (ref "SERIAL") (pin "7") (pinfunction "7_7") (pintype "input"))
    )
    (net (code "126") (name "unconnected-(SERIAL-Pad8)") (class "Default")
      (node (ref "SERIAL") (pin "8") (pinfunction "8_8") (pintype "input"))
    )
    (net (code "127") (name "unconnected-(SERIAL-Pad9)") (class "Default")
      (node (ref "SERIAL") (pin "9") (pinfunction "9_9") (pintype "input"))
    )
    (net (code "128") (name "unconnected-(VIA-CA1-Pad40)") (class "Default")
      (node (ref "VIA") (pin "40") (pinfunction "CA1_40") (pintype "bidirectional"))
    )
    (net (code "129") (name "unconnected-(VIA-CA2-Pad39)") (class "Default")
      (node (ref "VIA") (pin "39") (pinfunction "CA2_39") (pintype "bidirectional"))
    )
    (net (code "130") (name "unconnected-(VIA-CB1-Pad18)") (class "Default")
      (node (ref "VIA") (pin "18") (pinfunction "CB1_18") (pintype "bidirectional"))
    )
    (net (code "131") (name "unconnected-(VIA-CB2-Pad19)") (class "Default")
      (node (ref "VIA") (pin "19") (pinfunction "CB2_19") (pintype "output"))
    )
  )
)
